# 2ndOne.net
KiCad netlist of a schematic drawn in EAGLE
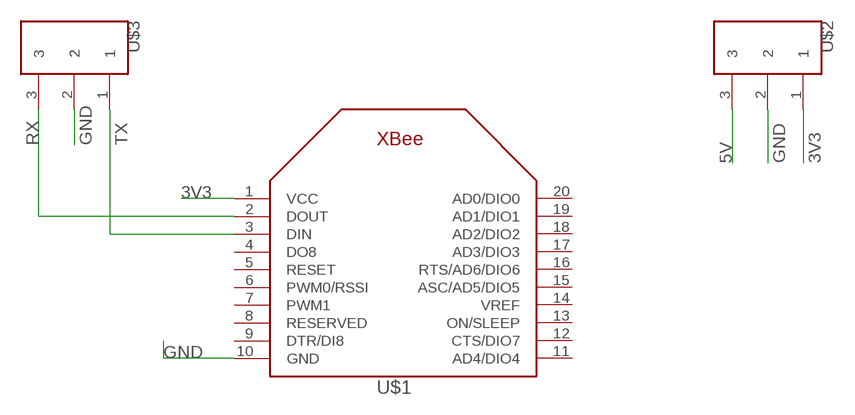
[diagram p0: schematic, sheet 1]

(export (version "E")
  (design (tool "Eeschema 10.0.6"))
  (components
    (comp (ref "U$1")
      (value "XBEE")
      (footprint "eagle-import:XBEE")
      (libsource (lib "eagle-import") (part "XBEE"))
    )
    (comp (ref "U$2")
      (value "PIN3")
      (footprint "eagle-import:3PIN")
      (libsource (lib "eagle-import") (part "PIN3"))
    )
    (comp (ref "U$3")
      (value "PIN3")
      (footprint "eagle-import:3PIN")
      (libsource (lib "eagle-import") (part "PIN3"))
    )
  )
  (nets
    (net (code "1") (name "/3V3") (class "Default")
      (node (ref "U$1") (pin "1") (pinfunction "VCC_1") (pintype "power_in"))
      (node (ref "U$2") (pin "1") (pinfunction "1_1") (pintype "bidirectional"))
    )
    (net (code "2") (name "/5V") (class "Default")
      (node (ref "U$2") (pin "3") (pinfunction "3_3") (pintype "bidirectional"))
    )
    (net (code "3") (name "/GND") (class "Default")
      (node (ref "U$1") (pin "10") (pinfunction "GND_10") (pintype "power_in"))
      (node (ref "U$2") (pin "2") (pinfunction "2_2") (pintype "bidirectional"))
      (node (ref "U$3") (pin "2") (pinfunction "2_2") (pintype "bidirectional"))
    )
    (net (code "4") (name "/RX") (class "Default")
      (node (ref "U$1") (pin "2") (pinfunction "DOUT_2") (pintype "output"))
      (node (ref "U$3") (pin "3") (pinfunction "3_3") (pintype "bidirectional"))
    )
    (net (code "5") (name "/TX") (class "Default")
      (node (ref "U$1") (pin "3") (pinfunction "DIN_3") (pintype "input"))
      (node (ref "U$3") (pin "1") (pinfunction "1_1") (pintype "bidirectional"))
    )
    (net (code "6") (name "unconnected-(U$1-AD0{slash}DIO0-Pad20)") (class "Default")
      (node (ref "U$1") (pin "20") (pinfunction "AD0/DIO0_20") (pintype "bidirectional"))
    )
    (net (code "7") (name "unconnected-(U$1-AD1{slash}DIO1-Pad19)") (class "Default")
      (node (ref "U$1") (pin "19") (pinfunction "AD1/DIO1_19") (pintype "bidirectional"))
    )
    (net (code "8") (name "unconnected-(U$1-AD2{slash}DIO2-Pad18)") (class "Default")
      (node (ref "U$1") (pin "18") (pinfunction "AD2/DIO2_18") (pintype "bidirectional"))
    )
    (net (code "9") (name "unconnected-(U$1-AD3{slash}DIO3-Pad17)") (class "Default")
      (node (ref "U$1") (pin "17") (pinfunction "AD3/DIO3_17") (pintype "bidirectional"))
    )
    (net (code "10") (name "unconnected-(U$1-AD4{slash}DIO4-Pad11)") (class "Default")
      (node (ref "U$1") (pin "11") (pinfunction "AD4/DIO4_11") (pintype "bidirectional"))
    )
    (net (code "11") (name "unconnected-(U$1-ASC{slash}AD5{slash}DIO5-Pad15)") (class "Default")
      (node (ref "U$1") (pin "15") (pinfunction "ASC/AD5/DIO5_15") (pintype "bidirectional"))
    )
    (net (code "12") (name "unconnected-(U$1-CTS{slash}DIO7-Pad12)") (class "Default")
      (node (ref "U$1") (pin "12") (pinfunction "CTS/DIO7_12") (pintype "bidirectional"))
    )
    (net (code "13") (name "unconnected-(U$1-DO8-Pad4)") (class "Default")
      (node (ref "U$1") (pin "4") (pinfunction "DO8_4") (pintype "output"))
    )
    (net (code "14") (name "unconnected-(U$1-DTR{slash}DI8-Pad9)") (class "Default")
      (node (ref "U$1") (pin "9") (pinfunction "DTR/DI8_9") (pintype "input"))
    )
    (net (code "15") (name "unconnected-(U$1-ON{slash}SLEEP-Pad13)") (class "Default")
      (node (ref "U$1") (pin "13") (pinfunction "ON/SLEEP_13") (pintype "output"))
    )
    (net (code "16") (name "unconnected-(U$1-PWM0{slash}RSSI-Pad6)") (class "Default")
      (node (ref "U$1") (pin "6") (pinfunction "PWM0/RSSI_6") (pintype "output"))
    )
    (net (code "17") (name "unconnected-(U$1-PWM1-Pad7)") (class "Default")
      (node (ref "U$1") (pin "7") (pinfunction "PWM1_7") (pintype "output"))
    )
    (net (code "18") (name "unconnected-(U$1-RESERVED-Pad8)") (class "Default")
      (node (ref "U$1") (pin "8") (pinfunction "RESERVED_8") (pintype "no_connect"))
    )
    (net (code "19") (name "unconnected-(U$1-RESET-Pad5)") (class "Default")
      (node (ref "U$1") (pin "5") (pinfunction "RESET_5") (pintype "input"))
    )
    (net (code "20") (name "unconnected-(U$1-RTS{slash}AD6{slash}DIO6-Pad16)") (class "Default")
      (node (ref "U$1") (pin "16") (pinfunction "RTS/AD6/DIO6_16") (pintype "bidirectional"))
    )
    (net (code "21") (name "unconnected-(U$1-VREF-Pad14)") (class "Default")
      (node (ref "U$1") (pin "14") (pinfunction "VREF_14") (pintype "input"))
    )
  )
)
